# Flow_sensor.net
KiCad netlist of a schematic drawn in Altium Designer
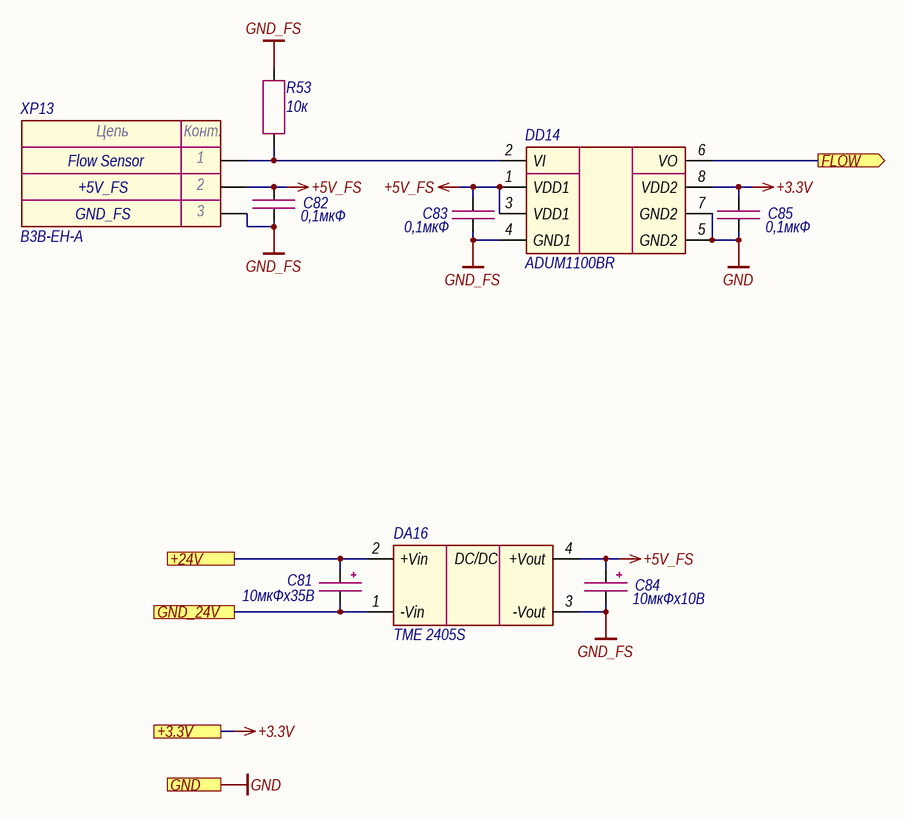
[diagram p0: Flow_sensor.SchDoc]

(export (version "E")
  (design (tool "Eeschema 10.0.6"))
  (components
    (comp (ref "C81")
      (value "10мкФх35B")
      (footprint "Pcb_library:CAP_C")
      (libsource (lib "Schem_library") (part "Capacitor_Polar"))
    )
    (comp (ref "C82")
      (value "0,1мкФ")
      (footprint "Pcb_library:CAP_0603")
      (fields (field (name "MANUFACTURER") "Murata"))
      (libsource (lib "Schem_library") (part "Capacitor"))
    )
    (comp (ref "C83")
      (value "0,1мкФ")
      (footprint "Pcb_library:CAP_0603")
      (fields (field (name "MANUFACTURER") "Murata"))
      (libsource (lib "Schem_library") (part "Capacitor"))
    )
    (comp (ref "C84")
      (value "10мкФх10B")
      (footprint "Pcb_library:CAP_A")
      (libsource (lib "Schem_library") (part "Capacitor_Polar"))
    )
    (comp (ref "C85")
      (value "0,1мкФ")
      (footprint "Pcb_library:CAP_0603")
      (fields (field (name "MANUFACTURER") "Murata"))
      (libsource (lib "Schem_library") (part "Capacitor"))
    )
    (comp (ref "DA16")
      (value "TME 2405S")
      (footprint "Pcb_library:TME (SIP-4)")
      (fields (field (name "MANUFACTURER") "Traco Power"))
      (libsource (lib "Schem_library") (part "TME"))
    )
    (comp (ref "DD14")
      (value "ADUM1100BR")
      (footprint "Pcb_library:SOIC-8")
      (fields (field (name "MANUFACTURER") "Analog Devices"))
      (libsource (lib "Schem_library") (part "ADUM1100"))
    )
    (comp (ref "R53")
      (value "10к")
      (footprint "Pcb_library:RES_0603")
      (fields (field (name "MANUFACTURER") "Yageo"))
      (libsource (lib "Schem_library") (part "Resistor"))
    )
    (comp (ref "XP13")
      (value "B3B-EH-A")
      (footprint "B3B-EH-A")
      (fields (field (name "MANUFACTURER") "JST"))
      (libsource (lib "Schem_library") (part "Connector-3"))
    )
  )
  (nets
    (net (code "1") (name "+3.3V") (class "Default")
      (node (ref "C85") (pin "1") (pinfunction "1_1") (pintype "passive"))
      (node (ref "DD14") (pin "8") (pinfunction "VDD2_8") (pintype "passive"))
    )
    (net (code "2") (name "+5V_FS") (class "Default")
      (node (ref "C82") (pin "1") (pinfunction "1_1") (pintype "passive"))
      (node (ref "C83") (pin "1") (pinfunction "1_1") (pintype "passive"))
      (node (ref "C84") (pin "1") (pinfunction "1_1") (pintype "passive"))
      (node (ref "DA16") (pin "4") (pinfunction "+Vout_4") (pintype "passive"))
      (node (ref "DD14") (pin "1") (pinfunction "VDD1_1") (pintype "passive"))
      (node (ref "DD14") (pin "3") (pinfunction "VDD1_3") (pintype "passive"))
      (node (ref "XP13") (pin "2") (pintype "passive"))
    )
    (net (code "3") (name "/+24V") (class "Default")
      (node (ref "C81") (pin "1") (pinfunction "1_1") (pintype "passive"))
      (node (ref "DA16") (pin "2") (pinfunction "+Vin_2") (pintype "passive"))
    )
    (net (code "4") (name "/FLOW") (class "Default")
      (node (ref "DD14") (pin "6") (pinfunction "VO_6") (pintype "passive"))
    )
    (net (code "5") (name "/GND_24V") (class "Default")
      (node (ref "C81") (pin "2") (pinfunction "2_2") (pintype "passive"))
      (node (ref "DA16") (pin "1") (pinfunction "-Vin_1") (pintype "passive"))
    )
    (net (code "6") (name "GND") (class "Default")
      (node (ref "C85") (pin "2") (pinfunction "2_2") (pintype "passive"))
      (node (ref "DD14") (pin "5") (pinfunction "GND2_5") (pintype "passive"))
      (node (ref "DD14") (pin "7") (pinfunction "GND2_7") (pintype "passive"))
    )
    (net (code "7") (name "GND_FS") (class "Default")
      (node (ref "C82") (pin "2") (pinfunction "2_2") (pintype "passive"))
      (node (ref "C83") (pin "2") (pinfunction "2_2") (pintype "passive"))
      (node (ref "C84") (pin "2") (pinfunction "2_2") (pintype "passive"))
      (node (ref "DA16") (pin "3") (pinfunction "-Vout_3") (pintype "passive"))
      (node (ref "DD14") (pin "4") (pinfunction "GND1_4") (pintype "passive"))
      (node (ref "R53") (pin "2") (pinfunction "2_2") (pintype "passive"))
      (node (ref "XP13") (pin "3") (pintype "passive"))
    )
    (net (code "8") (name "Net-(DD14-VI)") (class "Default")
      (node (ref "DD14") (pin "2") (pinfunction "VI_2") (pintype "passive"))
      (node (ref "R53") (pin "1") (pinfunction "1_1") (pintype "passive"))
      (node (ref "XP13") (pin "1") (pintype "passive"))
    )
  )
)
